# Bridge.net
KiCad netlist of a schematic drawn in Altium Designer
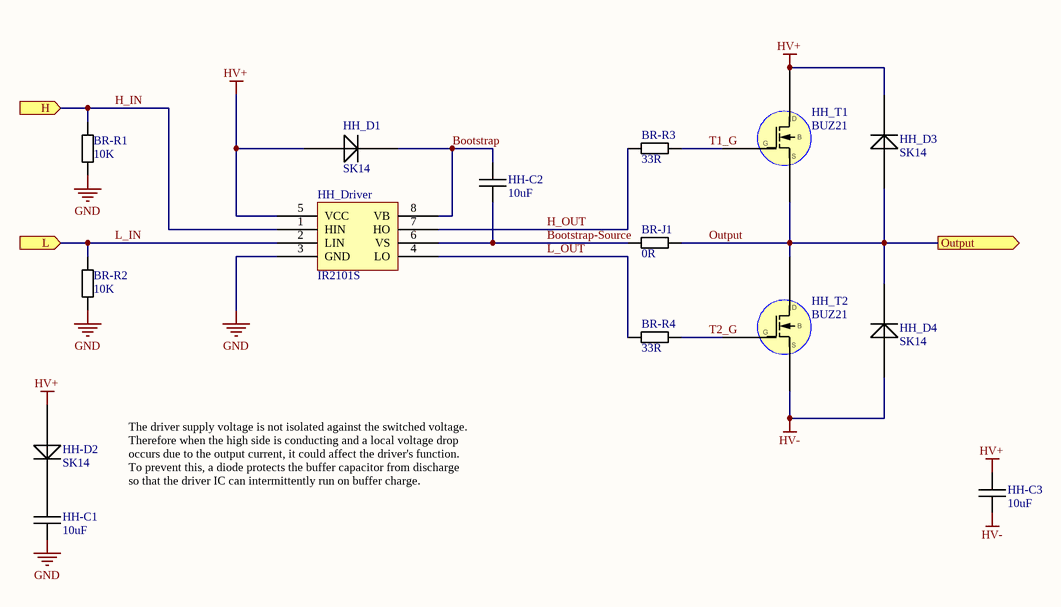
[diagram p0: Bridge.SchDoc]

(export (version "E")
  (design (tool "Eeschema 10.0.6"))
  (components
    (comp (ref "BR-J1")
      (value "0R")
      (footprint "R 0805 / 2012 wide")
      (libsource (lib "Standard") (part "Resistor"))
    )
    (comp (ref "BR-R1") (value "10K") (footprint "R 0805 / 2012") (libsource (lib "") (part "Resistor_1")))
    (comp (ref "BR-R2") (value "10K") (footprint "R 0805 / 2012") (libsource (lib "") (part "Resistor_1")))
    (comp (ref "BR-R3")
      (value "33R")
      (footprint "R 0805 / 2012")
      (libsource (lib "Standard") (part "Resistor"))
    )
    (comp (ref "BR-R4")
      (value "33R")
      (footprint "R 0805 / 2012")
      (libsource (lib "Standard") (part "Resistor"))
    )
    (comp (ref "HH-C1")
      (value "10uF")
      (footprint "C 0805 / 2012")
      (libsource (lib "Standard") (part "Capacitor"))
    )
    (comp (ref "HH-C2")
      (value "10uF")
      (footprint "C 0805 / 2012")
      (libsource (lib "Standard") (part "Capacitor"))
    )
    (comp (ref "HH-C3")
      (value "10uF")
      (footprint "Header 1x2+1 1.0mm")
      (libsource (lib "Standard") (part "Capacitor"))
    )
    (comp (ref "HH-D2") (value "SK14") (footprint "SC-90") (libsource (lib "Standard") (part "Diode")))
    (comp (ref "HH_D1") (value "SK14") (footprint "SC-90") (libsource (lib "Standard") (part "Diode")))
    (comp (ref "HH_D3") (value "SK14") (footprint "SC-90") (libsource (lib "Standard") (part "Diode")))
    (comp (ref "HH_D4") (value "SK14") (footprint "SC-90") (libsource (lib "Standard") (part "Diode")))
    (comp (ref "HH_Driver")
      (value "IR2101S")
      (footprint "SOIC-8")
      (description "High and Low Side Driver")
      (libsource (lib "ICs") (part "IR21xx"))
    )
    (comp (ref "HH_T1")
      (value "BUZ21")
      (footprint "TO-220 AB")
      (description "Enhancement Type")
      (libsource (lib "ICs") (part "FET N-Channel"))
    )
    (comp (ref "HH_T2")
      (value "BUZ21")
      (footprint "TO-220 AB")
      (description "Enhancement Type")
      (libsource (lib "ICs") (part "FET N-Channel"))
    )
  )
  (nets
    (net (code "1") (name "/Bootstrap") (class "Default")
      (node (ref "HH-C2") (pin "1") (pinfunction "1_1") (pintype "passive"))
      (node (ref "HH_D1") (pin "1") (pinfunction "1_1") (pintype "passive"))
      (node (ref "HH_Driver") (pin "8") (pinfunction "VB_8") (pintype "passive"))
    )
    (net (code "2") (name "/Bootstrap-Source") (class "Default")
      (node (ref "BR-J1") (pin "1") (pinfunction "1_1") (pintype "passive"))
      (node (ref "HH-C2") (pin "2") (pinfunction "1_2") (pintype "passive"))
      (node (ref "HH_Driver") (pin "6") (pinfunction "VS_6") (pintype "passive"))
    )
    (net (code "3") (name "/H_IN") (class "Default")
      (node (ref "BR-R1") (pin "2") (pinfunction "2_2") (pintype "passive"))
      (node (ref "HH_Driver") (pin "1") (pinfunction "HIN_1") (pintype "passive"))
    )
    (net (code "4") (name "/H_OUT") (class "Default")
      (node (ref "BR-R3") (pin "1") (pinfunction "1_1") (pintype "passive"))
      (node (ref "HH_Driver") (pin "7") (pinfunction "HO_7") (pintype "passive"))
    )
    (net (code "5") (name "/L_IN") (class "Default")
      (node (ref "BR-R2") (pin "2") (pinfunction "2_2") (pintype "passive"))
      (node (ref "HH_Driver") (pin "2") (pinfunction "LIN_2") (pintype "passive"))
    )
    (net (code "6") (name "/L_OUT") (class "Default")
      (node (ref "BR-R4") (pin "1") (pinfunction "1_1") (pintype "passive"))
      (node (ref "HH_Driver") (pin "4") (pinfunction "LO_4") (pintype "passive"))
    )
    (net (code "7") (name "/Output") (class "Default")
      (node (ref "BR-J1") (pin "2") (pinfunction "2_2") (pintype "passive"))
      (node (ref "HH_D3") (pin "2") (pinfunction "2_2") (pintype "passive"))
      (node (ref "HH_D4") (pin "1") (pinfunction "1_1") (pintype "passive"))
      (node (ref "HH_T1") (pin "3") (pinfunction "3_3") (pintype "passive"))
      (node (ref "HH_T2") (pin "2") (pinfunction "2_2") (pintype "passive"))
    )
    (net (code "8") (name "/T1_G") (class "Default")
      (node (ref "BR-R3") (pin "2") (pinfunction "2_2") (pintype "passive"))
      (node (ref "HH_T1") (pin "1") (pinfunction "1_1") (pintype "passive"))
    )
    (net (code "9") (name "/T2_G") (class "Default")
      (node (ref "BR-R4") (pin "2") (pinfunction "2_2") (pintype "passive"))
      (node (ref "HH_T2") (pin "1") (pinfunction "1_1") (pintype "passive"))
    )
    (net (code "10") (name "GND") (class "Default")
      (node (ref "BR-R1") (pin "1") (pinfunction "1_1") (pintype "passive"))
      (node (ref "BR-R2") (pin "1") (pinfunction "1_1") (pintype "passive"))
      (node (ref "HH-C1") (pin "2") (pinfunction "1_2") (pintype "passive"))
      (node (ref "HH_Driver") (pin "3") (pinfunction "GND_3") (pintype "passive"))
    )
    (net (code "11") (name "HV+") (class "Default")
      (node (ref "HH-C3") (pin "1") (pinfunction "1_1") (pintype "passive"))
      (node (ref "HH-D2") (pin "2") (pinfunction "2_2") (pintype "passive"))
      (node (ref "HH_D1") (pin "2") (pinfunction "2_2") (pintype "passive"))
      (node (ref "HH_D3") (pin "1") (pinfunction "1_1") (pintype "passive"))
      (node (ref "HH_Driver") (pin "5") (pinfunction "VCC_5") (pintype "passive"))
      (node (ref "HH_T1") (pin "2") (pinfunction "2_2") (pintype "passive"))
    )
    (net (code "12") (name "HV-") (class "Default")
      (node (ref "HH-C3") (pin "2") (pinfunction "1_2") (pintype "passive"))
      (node (ref "HH_D4") (pin "2") (pinfunction "2_2") (pintype "passive"))
      (node (ref "HH_T2") (pin "3") (pinfunction "3_3") (pintype "passive"))
    )
    (net (code "13") (name "Net-(HH-C1-Pad1)") (class "Default")
      (node (ref "HH-C1") (pin "1") (pinfunction "1_1") (pintype "passive"))
      (node (ref "HH-D2") (pin "1") (pinfunction "1_1") (pintype "passive"))
    )
  )
)
